# avrpwm.net
KiCad netlist of a schematic drawn in EAGLE
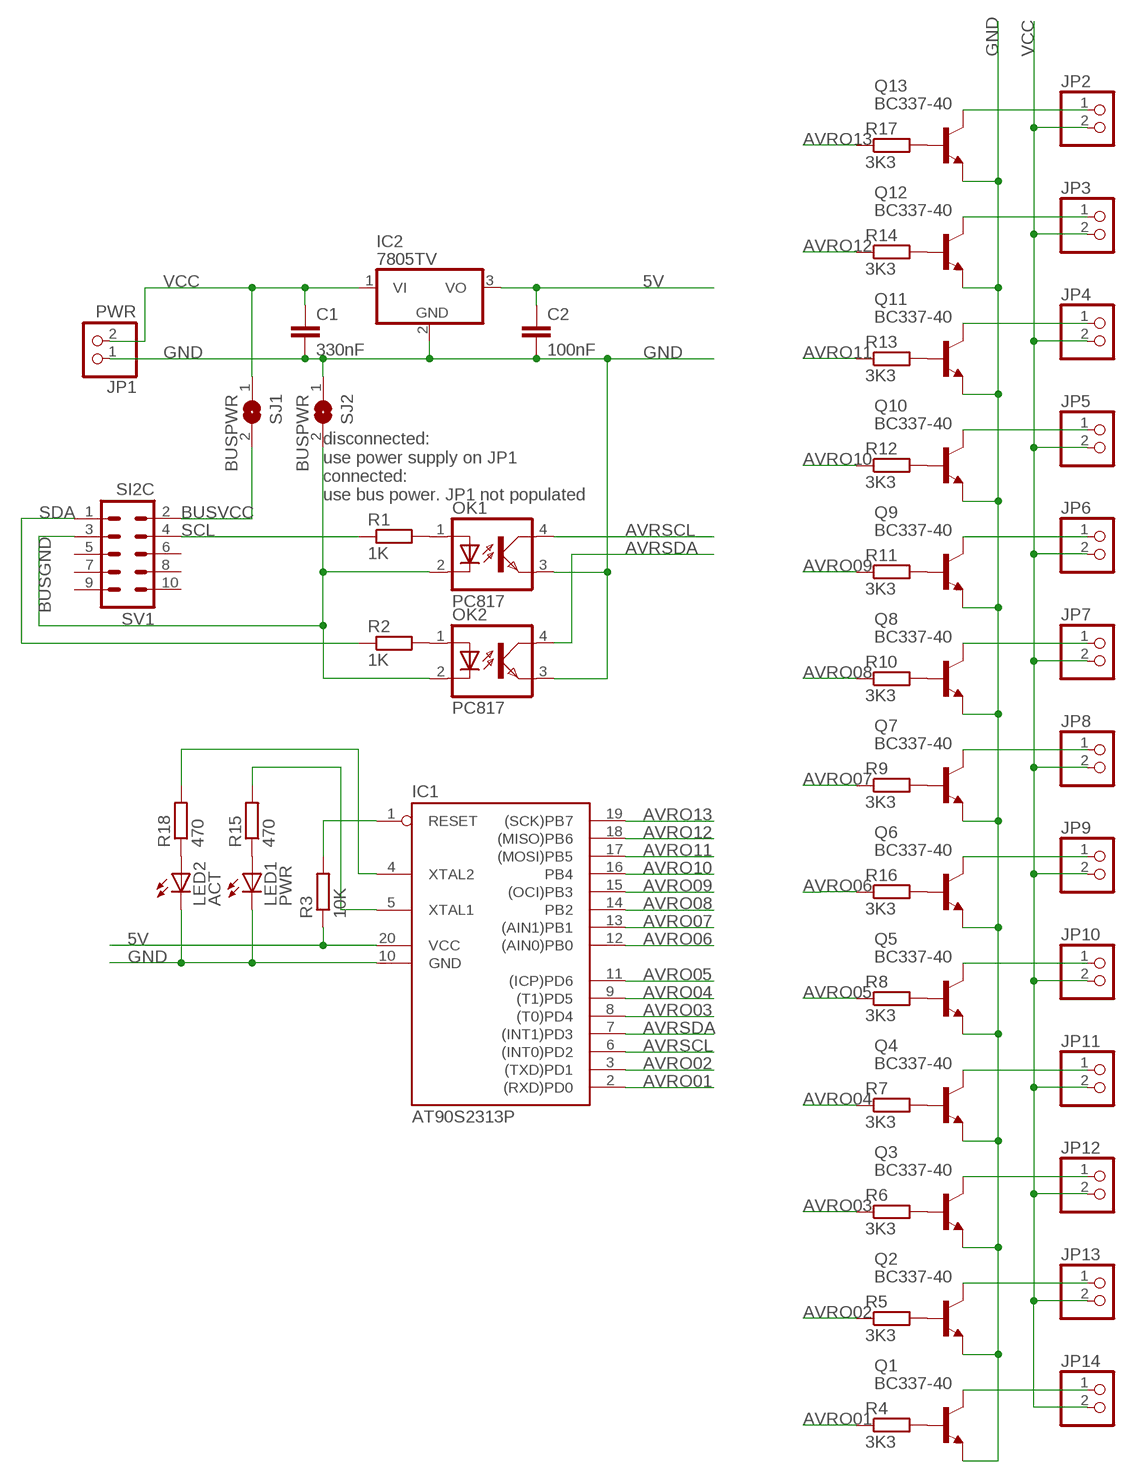
[diagram p0: schematic, sheet 1]

(export (version "E")
  (design (tool "Eeschema 10.0.6"))
  (components
    (comp (ref "C1")
      (value "330nF")
      (footprint "eagle-import:C2.5-3")
      (libsource (lib "eagle-import") (part "C2,5-3"))
    )
    (comp (ref "C2")
      (value "100nF")
      (footprint "eagle-import:C2.5-3")
      (libsource (lib "eagle-import") (part "C2,5-3"))
    )
    (comp (ref "IC1")
      (value "AT90S2313P")
      (footprint "eagle-import:DIL20")
      (libsource (lib "eagle-import") (part "AT90S2313P"))
    )
    (comp (ref "IC2")
      (value "7805TV")
      (footprint "eagle-import:TO220V")
      (libsource (lib "eagle-import") (part "78TV05"))
    )
    (comp (ref "JP1")
      (value "PWR")
      (footprint "eagle-import:1X02")
      (libsource (lib "eagle-import") (part "PINHD-1X2"))
    )
    (comp (ref "JP2")
      (value "PINHD-1X2")
      (footprint "eagle-import:1X02")
      (libsource (lib "eagle-import") (part "PINHD-1X2"))
    )
    (comp (ref "JP3")
      (value "PINHD-1X2")
      (footprint "eagle-import:1X02")
      (libsource (lib "eagle-import") (part "PINHD-1X2"))
    )
    (comp (ref "JP4")
      (value "PINHD-1X2")
      (footprint "eagle-import:1X02")
      (libsource (lib "eagle-import") (part "PINHD-1X2"))
    )
    (comp (ref "JP5")
      (value "PINHD-1X2")
      (footprint "eagle-import:1X02")
      (libsource (lib "eagle-import") (part "PINHD-1X2"))
    )
    (comp (ref "JP6")
      (value "PINHD-1X2")
      (footprint "eagle-import:1X02")
      (libsource (lib "eagle-import") (part "PINHD-1X2"))
    )
    (comp (ref "JP7")
      (value "PINHD-1X2")
      (footprint "eagle-import:1X02")
      (libsource (lib "eagle-import") (part "PINHD-1X2"))
    )
    (comp (ref "JP8")
      (value "PINHD-1X2")
      (footprint "eagle-import:1X02")
      (libsource (lib "eagle-import") (part "PINHD-1X2"))
    )
    (comp (ref "JP9")
      (value "PINHD-1X2")
      (footprint "eagle-import:1X02")
      (libsource (lib "eagle-import") (part "PINHD-1X2"))
    )
    (comp (ref "JP10")
      (value "PINHD-1X2")
      (footprint "eagle-import:1X02")
      (libsource (lib "eagle-import") (part "PINHD-1X2"))
    )
    (comp (ref "JP11")
      (value "PINHD-1X2")
      (footprint "eagle-import:1X02")
      (libsource (lib "eagle-import") (part "PINHD-1X2"))
    )
    (comp (ref "JP12")
      (value "PINHD-1X2")
      (footprint "eagle-import:1X02")
      (libsource (lib "eagle-import") (part "PINHD-1X2"))
    )
    (comp (ref "JP13")
      (value "PINHD-1X2")
      (footprint "eagle-import:1X02")
      (libsource (lib "eagle-import") (part "PINHD-1X2"))
    )
    (comp (ref "JP14")
      (value "PINHD-1X2")
      (footprint "eagle-import:1X02")
      (libsource (lib "eagle-import") (part "PINHD-1X2"))
    )
    (comp (ref "LED1")
      (value "PWR")
      (footprint "eagle-import:LED3MM")
      (libsource (lib "eagle-import") (part "LED3MM"))
    )
    (comp (ref "LED2")
      (value "ACT")
      (footprint "eagle-import:LED3MM")
      (libsource (lib "eagle-import") (part "LED3MM"))
    )
    (comp (ref "OK1")
      (value "PC817")
      (footprint "eagle-import:DIL04")
      (fields (field (name "MPN") "PC817X4J000F"))
      (libsource (lib "eagle-import") (part "PC817"))
    )
    (comp (ref "OK2")
      (value "PC817")
      (footprint "eagle-import:DIL04")
      (fields (field (name "MPN") "PC817X4J000F"))
      (libsource (lib "eagle-import") (part "PC817"))
    )
    (comp (ref "Q1")
      (value "BC337-40")
      (footprint "eagle-import:TO92")
      (libsource (lib "eagle-import") (part "BC337-40"))
    )
    (comp (ref "Q2")
      (value "BC337-40")
      (footprint "eagle-import:TO92")
      (libsource (lib "eagle-import") (part "BC337-40"))
    )
    (comp (ref "Q3")
      (value "BC337-40")
      (footprint "eagle-import:TO92")
      (libsource (lib "eagle-import") (part "BC337-40"))
    )
    (comp (ref "Q4")
      (value "BC337-40")
      (footprint "eagle-import:TO92")
      (libsource (lib "eagle-import") (part "BC337-40"))
    )
    (comp (ref "Q5")
      (value "BC337-40")
      (footprint "eagle-import:TO92")
      (libsource (lib "eagle-import") (part "BC337-40"))
    )
    (comp (ref "Q6")
      (value "BC337-40")
      (footprint "eagle-import:TO92")
      (libsource (lib "eagle-import") (part "BC337-40"))
    )
    (comp (ref "Q7")
      (value "BC337-40")
      (footprint "eagle-import:TO92")
      (libsource (lib "eagle-import") (part "BC337-40"))
    )
    (comp (ref "Q8")
      (value "BC337-40")
      (footprint "eagle-import:TO92")
      (libsource (lib "eagle-import") (part "BC337-40"))
    )
    (comp (ref "Q9")
      (value "BC337-40")
      (footprint "eagle-import:TO92")
      (libsource (lib "eagle-import") (part "BC337-40"))
    )
    (comp (ref "Q10")
      (value "BC337-40")
      (footprint "eagle-import:TO92")
      (libsource (lib "eagle-import") (part "BC337-40"))
    )
    (comp (ref "Q11")
      (value "BC337-40")
      (footprint "eagle-import:TO92")
      (libsource (lib "eagle-import") (part "BC337-40"))
    )
    (comp (ref "Q12")
      (value "BC337-40")
      (footprint "eagle-import:TO92")
      (libsource (lib "eagle-import") (part "BC337-40"))
    )
    (comp (ref "Q13")
      (value "BC337-40")
      (footprint "eagle-import:TO92")
      (libsource (lib "eagle-import") (part "BC337-40"))
    )
    (comp (ref "R1")
      (value "1K")
      (footprint "eagle-import:0207_10")
      (libsource (lib "eagle-import") (part "R-EU_0207/10"))
    )
    (comp (ref "R2")
      (value "1K")
      (footprint "eagle-import:0207_10")
      (libsource (lib "eagle-import") (part "R-EU_0207/10"))
    )
    (comp (ref "R3")
      (value "10K")
      (footprint "eagle-import:0207_10")
      (libsource (lib "eagle-import") (part "R-EU_0207/10"))
    )
    (comp (ref "R4")
      (value "3K3")
      (footprint "eagle-import:0207_10")
      (libsource (lib "eagle-import") (part "R-EU_0207/10"))
    )
    (comp (ref "R5")
      (value "3K3")
      (footprint "eagle-import:0207_10")
      (libsource (lib "eagle-import") (part "R-EU_0207/10"))
    )
    (comp (ref "R6")
      (value "3K3")
      (footprint "eagle-import:0207_10")
      (libsource (lib "eagle-import") (part "R-EU_0207/10"))
    )
    (comp (ref "R7")
      (value "3K3")
      (footprint "eagle-import:0207_10")
      (libsource (lib "eagle-import") (part "R-EU_0207/10"))
    )
    (comp (ref "R8")
      (value "3K3")
      (footprint "eagle-import:0207_10")
      (libsource (lib "eagle-import") (part "R-EU_0207/10"))
    )
    (comp (ref "R9")
      (value "3K3")
      (footprint "eagle-import:0207_10")
      (libsource (lib "eagle-import") (part "R-EU_0207/10"))
    )
    (comp (ref "R10")
      (value "3K3")
      (footprint "eagle-import:0207_10")
      (libsource (lib "eagle-import") (part "R-EU_0207/10"))
    )
    (comp (ref "R11")
      (value "3K3")
      (footprint "eagle-import:0207_10")
      (libsource (lib "eagle-import") (part "R-EU_0207/10"))
    )
    (comp (ref "R12")
      (value "3K3")
      (footprint "eagle-import:0207_10")
      (libsource (lib "eagle-import") (part "R-EU_0207/10"))
    )
    (comp (ref "R13")
      (value "3K3")
      (footprint "eagle-import:0207_10")
      (libsource (lib "eagle-import") (part "R-EU_0207/10"))
    )
    (comp (ref "R14")
      (value "3K3")
      (footprint "eagle-import:0207_10")
      (libsource (lib "eagle-import") (part "R-EU_0207/10"))
    )
    (comp (ref "R15")
      (value "470")
      (footprint "eagle-import:0207_10")
      (libsource (lib "eagle-import") (part "R-EU_0207/10"))
    )
    (comp (ref "R16")
      (value "3K3")
      (footprint "eagle-import:0207_10")
      (libsource (lib "eagle-import") (part "R-EU_0207/10"))
    )
    (comp (ref "R17")
      (value "3K3")
      (footprint "eagle-import:0207_10")
      (libsource (lib "eagle-import") (part "R-EU_0207/10"))
    )
    (comp (ref "R18")
      (value "470")
      (footprint "eagle-import:0207_10")
      (libsource (lib "eagle-import") (part "R-EU_0207/10"))
    )
    (comp (ref "SJ1")
      (value "BUSPWR")
      (footprint "eagle-import:SJ")
      (libsource (lib "eagle-import") (part "SJ"))
    )
    (comp (ref "SJ2")
      (value "BUSPWR")
      (footprint "eagle-import:SJ")
      (libsource (lib "eagle-import") (part "SJ"))
    )
    (comp (ref "SV1")
      (value "SI2C")
      (footprint "eagle-import:ML10")
      (libsource (lib "eagle-import") (part "ML10"))
    )
  )
  (nets
    (net (code "1") (name "/5V") (class "Default")
      (node (ref "C2") (pin "1") (pinfunction "1_1") (pintype "passive"))
      (node (ref "IC1") (pin "20") (pinfunction "VCC_20") (pintype "power_in"))
      (node (ref "IC2") (pin "3") (pinfunction "VO_3") (pintype "passive"))
      (node (ref "R3") (pin "1") (pinfunction "1_1") (pintype "passive"))
    )
    (net (code "2") (name "/AVRO01") (class "Default")
      (node (ref "IC1") (pin "2") (pinfunction "(RXD)PD0_2") (pintype "bidirectional"))
      (node (ref "R4") (pin "1") (pinfunction "1_1") (pintype "passive"))
    )
    (net (code "3") (name "/AVRO02") (class "Default")
      (node (ref "IC1") (pin "3") (pinfunction "(TXD)PD1_3") (pintype "bidirectional"))
      (node (ref "R5") (pin "1") (pinfunction "1_1") (pintype "passive"))
    )
    (net (code "4") (name "/AVRO03") (class "Default")
      (node (ref "IC1") (pin "8") (pinfunction "(T0)PD4_8") (pintype "bidirectional"))
      (node (ref "R6") (pin "1") (pinfunction "1_1") (pintype "passive"))
    )
    (net (code "5") (name "/AVRO04") (class "Default")
      (node (ref "IC1") (pin "9") (pinfunction "(T1)PD5_9") (pintype "bidirectional"))
      (node (ref "R7") (pin "1") (pinfunction "1_1") (pintype "passive"))
    )
    (net (code "6") (name "/AVRO05") (class "Default")
      (node (ref "IC1") (pin "11") (pinfunction "(ICP)PD6_11") (pintype "bidirectional"))
      (node (ref "R8") (pin "1") (pinfunction "1_1") (pintype "passive"))
    )
    (net (code "7") (name "/AVRO06") (class "Default")
      (node (ref "IC1") (pin "12") (pinfunction "(AIN0)PB0_12") (pintype "bidirectional"))
      (node (ref "R16") (pin "1") (pinfunction "1_1") (pintype "passive"))
    )
    (net (code "8") (name "/AVRO07") (class "Default")
      (node (ref "IC1") (pin "13") (pinfunction "(AIN1)PB1_13") (pintype "bidirectional"))
      (node (ref "R9") (pin "1") (pinfunction "1_1") (pintype "passive"))
    )
    (net (code "9") (name "/AVRO08") (class "Default")
      (node (ref "IC1") (pin "14") (pinfunction "PB2_14") (pintype "bidirectional"))
      (node (ref "R10") (pin "1") (pinfunction "1_1") (pintype "passive"))
    )
    (net (code "10") (name "/AVRO09") (class "Default")
      (node (ref "IC1") (pin "15") (pinfunction "(OCI)PB3_15") (pintype "bidirectional"))
      (node (ref "R11") (pin "1") (pinfunction "1_1") (pintype "passive"))
    )
    (net (code "11") (name "/AVRO10") (class "Default")
      (node (ref "IC1") (pin "16") (pinfunction "PB4_16") (pintype "bidirectional"))
      (node (ref "R12") (pin "1") (pinfunction "1_1") (pintype "passive"))
    )
    (net (code "12") (name "/AVRO11") (class "Default")
      (node (ref "IC1") (pin "17") (pinfunction "(MOSI)PB5_17") (pintype "bidirectional"))
      (node (ref "R13") (pin "1") (pinfunction "1_1") (pintype "passive"))
    )
    (net (code "13") (name "/AVRO12") (class "Default")
      (node (ref "IC1") (pin "18") (pinfunction "(MISO)PB6_18") (pintype "bidirectional"))
      (node (ref "R14") (pin "1") (pinfunction "1_1") (pintype "passive"))
    )
    (net (code "14") (name "/AVRO13") (class "Default")
      (node (ref "IC1") (pin "19") (pinfunction "(SCK)PB7_19") (pintype "bidirectional"))
      (node (ref "R17") (pin "1") (pinfunction "1_1") (pintype "passive"))
    )
    (net (code "15") (name "/AVRSCL") (class "Default")
      (node (ref "IC1") (pin "6") (pinfunction "(INT0)PD2_6") (pintype "bidirectional"))
      (node (ref "OK1") (pin "4") (pinfunction "COL_4") (pintype "passive"))
    )
    (net (code "16") (name "/AVRSDA") (class "Default")
      (node (ref "IC1") (pin "7") (pinfunction "(INT1)PD3_7") (pintype "bidirectional"))
      (node (ref "OK2") (pin "4") (pinfunction "COL_4") (pintype "passive"))
    )
    (net (code "17") (name "/BUSGND") (class "Default")
      (node (ref "OK1") (pin "2") (pinfunction "C_2") (pintype "passive"))
      (node (ref "OK2") (pin "2") (pinfunction "C_2") (pintype "passive"))
      (node (ref "SJ2") (pin "2") (pinfunction "2_2") (pintype "passive"))
      (node (ref "SV1") (pin "3") (pinfunction "3_3") (pintype "passive"))
    )
    (net (code "18") (name "/BUSVCC") (class "Default")
      (node (ref "SJ1") (pin "2") (pinfunction "2_2") (pintype "passive"))
      (node (ref "SV1") (pin "2") (pinfunction "2_2") (pintype "passive"))
    )
    (net (code "19") (name "/GND") (class "Default")
      (node (ref "C1") (pin "2") (pinfunction "2_2") (pintype "passive"))
      (node (ref "C2") (pin "2") (pinfunction "2_2") (pintype "passive"))
      (node (ref "IC1") (pin "10") (pinfunction "GND_10") (pintype "power_in"))
      (node (ref "IC2") (pin "2") (pinfunction "GND_2") (pintype "passive"))
      (node (ref "JP1") (pin "1") (pinfunction "1_1") (pintype "passive"))
      (node (ref "LED1") (pin "K") (pinfunction "C_K") (pintype "passive"))
      (node (ref "LED2") (pin "K") (pinfunction "C_K") (pintype "passive"))
      (node (ref "OK1") (pin "3") (pinfunction "EMIT_3") (pintype "passive"))
      (node (ref "OK2") (pin "3") (pinfunction "EMIT_3") (pintype "passive"))
      (node (ref "Q1") (pin "1") (pinfunction "E_1") (pintype "passive"))
      (node (ref "Q10") (pin "1") (pinfunction "E_1") (pintype "passive"))
      (node (ref "Q11") (pin "1") (pinfunction "E_1") (pintype "passive"))
      (node (ref "Q12") (pin "1") (pinfunction "E_1") (pintype "passive"))
      (node (ref "Q13") (pin "1") (pinfunction "E_1") (pintype "passive"))
      (node (ref "Q2") (pin "1") (pinfunction "E_1") (pintype "passive"))
      (node (ref "Q3") (pin "1") (pinfunction "E_1") (pintype "passive"))
      (node (ref "Q4") (pin "1") (pinfunction "E_1") (pintype "passive"))
      (node (ref "Q5") (pin "1") (pinfunction "E_1") (pintype "passive"))
      (node (ref "Q6") (pin "1") (pinfunction "E_1") (pintype "passive"))
      (node (ref "Q7") (pin "1") (pinfunction "E_1") (pintype "passive"))
      (node (ref "Q8") (pin "1") (pinfunction "E_1") (pintype "passive"))
      (node (ref "Q9") (pin "1") (pinfunction "E_1") (pintype "passive"))
      (node (ref "SJ2") (pin "1") (pinfunction "1_1") (pintype "passive"))
    )
    (net (code "20") (name "/SCL") (class "Default")
      (node (ref "R1") (pin "1") (pinfunction "1_1") (pintype "passive"))
      (node (ref "SV1") (pin "4") (pinfunction "4_4") (pintype "passive"))
    )
    (net (code "21") (name "/SDA") (class "Default")
      (node (ref "R2") (pin "1") (pinfunction "1_1") (pintype "passive"))
      (node (ref "SV1") (pin "1") (pinfunction "1_1") (pintype "passive"))
    )
    (net (code "22") (name "/VCC") (class "Default")
      (node (ref "C1") (pin "1") (pinfunction "1_1") (pintype "passive"))
      (node (ref "IC2") (pin "1") (pinfunction "VI_1") (pintype "input"))
      (node (ref "JP1") (pin "2") (pinfunction "2_2") (pintype "passive"))
      (node (ref "JP10") (pin "2") (pinfunction "2_2") (pintype "passive"))
      (node (ref "JP11") (pin "2") (pinfunction "2_2") (pintype "passive"))
      (node (ref "JP12") (pin "2") (pinfunction "2_2") (pintype "passive"))
      (node (ref "JP13") (pin "2") (pinfunction "2_2") (pintype "passive"))
      (node (ref "JP14") (pin "2") (pinfunction "2_2") (pintype "passive"))
      (node (ref "JP2") (pin "2") (pinfunction "2_2") (pintype "passive"))
      (node (ref "JP3") (pin "2") (pinfunction "2_2") (pintype "passive"))
      (node (ref "JP4") (pin "2") (pinfunction "2_2") (pintype "passive"))
      (node (ref "JP5") (pin "2") (pinfunction "2_2") (pintype "passive"))
      (node (ref "JP6") (pin "2") (pinfunction "2_2") (pintype "passive"))
      (node (ref "JP7") (pin "2") (pinfunction "2_2") (pintype "passive"))
      (node (ref "JP8") (pin "2") (pinfunction "2_2") (pintype "passive"))
      (node (ref "JP9") (pin "2") (pinfunction "2_2") (pintype "passive"))
      (node (ref "SJ1") (pin "1") (pinfunction "1_1") (pintype "passive"))
    )
    (net (code "23") (name "Net-(IC1-RESET)") (class "Default")
      (node (ref "IC1") (pin "1") (pinfunction "RESET_1") (pintype "bidirectional"))
      (node (ref "R3") (pin "2") (pinfunction "2_2") (pintype "passive"))
    )
    (net (code "24") (name "Net-(IC1-XTAL1)") (class "Default")
      (node (ref "IC1") (pin "5") (pinfunction "XTAL1_5") (pintype "bidirectional"))
      (node (ref "R15") (pin "2") (pinfunction "2_2") (pintype "passive"))
    )
    (net (code "25") (name "Net-(IC1-XTAL2)") (class "Default")
      (node (ref "IC1") (pin "4") (pinfunction "XTAL2_4") (pintype "bidirectional"))
      (node (ref "R18") (pin "2") (pinfunction "2_2") (pintype "passive"))
    )
    (net (code "26") (name "Net-(LED1-PadA)") (class "Default")
      (node (ref "LED1") (pin "A") (pinfunction "A_A") (pintype "passive"))
      (node (ref "R15") (pin "1") (pinfunction "1_1") (pintype "passive"))
    )
    (net (code "27") (name "Net-(LED2-PadA)") (class "Default")
      (node (ref "LED2") (pin "A") (pinfunction "A_A") (pintype "passive"))
      (node (ref "R18") (pin "1") (pinfunction "1_1") (pintype "passive"))
    )
    (net (code "28") (name "Net-(OK1-A)") (class "Default")
      (node (ref "OK1") (pin "1") (pinfunction "A_1") (pintype "passive"))
      (node (ref "R1") (pin "2") (pinfunction "2_2") (pintype "passive"))
    )
    (net (code "29") (name "Net-(OK2-A)") (class "Default")
      (node (ref "OK2") (pin "1") (pinfunction "A_1") (pintype "passive"))
      (node (ref "R2") (pin "2") (pinfunction "2_2") (pintype "passive"))
    )
    (net (code "30") (name "Net-(Q1-B)") (class "Default")
      (node (ref "Q1") (pin "2") (pinfunction "B_2") (pintype "passive"))
      (node (ref "R4") (pin "2") (pinfunction "2_2") (pintype "passive"))
    )
    (net (code "31") (name "Net-(Q1-C)") (class "Default")
      (node (ref "JP14") (pin "1") (pinfunction "1_1") (pintype "passive"))
      (node (ref "Q1") (pin "3") (pinfunction "C_3") (pintype "passive"))
    )
    (net (code "32") (name "Net-(Q2-B)") (class "Default")
      (node (ref "Q2") (pin "2") (pinfunction "B_2") (pintype "passive"))
      (node (ref "R5") (pin "2") (pinfunction "2_2") (pintype "passive"))
    )
    (net (code "33") (name "Net-(Q2-C)") (class "Default")
      (node (ref "JP13") (pin "1") (pinfunction "1_1") (pintype "passive"))
      (node (ref "Q2") (pin "3") (pinfunction "C_3") (pintype "passive"))
    )
    (net (code "34") (name "Net-(Q3-B)") (class "Default")
      (node (ref "Q3") (pin "2") (pinfunction "B_2") (pintype "passive"))
      (node (ref "R6") (pin "2") (pinfunction "2_2") (pintype "passive"))
    )
    (net (code "35") (name "Net-(Q3-C)") (class "Default")
      (node (ref "JP12") (pin "1") (pinfunction "1_1") (pintype "passive"))
      (node (ref "Q3") (pin "3") (pinfunction "C_3") (pintype "passive"))
    )
    (net (code "36") (name "Net-(Q4-B)") (class "Default")
      (node (ref "Q4") (pin "2") (pinfunction "B_2") (pintype "passive"))
      (node (ref "R7") (pin "2") (pinfunction "2_2") (pintype "passive"))
    )
    (net (code "37") (name "Net-(Q4-C)") (class "Default")
      (node (ref "JP11") (pin "1") (pinfunction "1_1") (pintype "passive"))
      (node (ref "Q4") (pin "3") (pinfunction "C_3") (pintype "passive"))
    )
    (net (code "38") (name "Net-(Q5-B)") (class "Default")
      (node (ref "Q5") (pin "2") (pinfunction "B_2") (pintype "passive"))
      (node (ref "R8") (pin "2") (pinfunction "2_2") (pintype "passive"))
    )
    (net (code "39") (name "Net-(Q5-C)") (class "Default")
      (node (ref "JP10") (pin "1") (pinfunction "1_1") (pintype "passive"))
      (node (ref "Q5") (pin "3") (pinfunction "C_3") (pintype "passive"))
    )
    (net (code "40") (name "Net-(Q6-B)") (class "Default")
      (node (ref "Q6") (pin "2") (pinfunction "B_2") (pintype "passive"))
      (node (ref "R16") (pin "2") (pinfunction "2_2") (pintype "passive"))
    )
    (net (code "41") (name "Net-(Q6-C)") (class "Default")
      (node (ref "JP9") (pin "1") (pinfunction "1_1") (pintype "passive"))
      (node (ref "Q6") (pin "3") (pinfunction "C_3") (pintype "passive"))
    )
    (net (code "42") (name "Net-(Q7-B)") (class "Default")
      (node (ref "Q7") (pin "2") (pinfunction "B_2") (pintype "passive"))
      (node (ref "R9") (pin "2") (pinfunction "2_2") (pintype "passive"))
    )
    (net (code "43") (name "Net-(Q7-C)") (class "Default")
      (node (ref "JP8") (pin "1") (pinfunction "1_1") (pintype "passive"))
      (node (ref "Q7") (pin "3") (pinfunction "C_3") (pintype "passive"))
    )
    (net (code "44") (name "Net-(Q8-B)") (class "Default")
      (node (ref "Q8") (pin "2") (pinfunction "B_2") (pintype "passive"))
      (node (ref "R10") (pin "2") (pinfunction "2_2") (pintype "passive"))
    )
    (net (code "45") (name "Net-(Q8-C)") (class "Default")
      (node (ref "JP7") (pin "1") (pinfunction "1_1") (pintype "passive"))
      (node (ref "Q8") (pin "3") (pinfunction "C_3") (pintype "passive"))
    )
    (net (code "46") (name "Net-(Q9-B)") (class "Default")
      (node (ref "Q9") (pin "2") (pinfunction "B_2") (pintype "passive"))
      (node (ref "R11") (pin "2") (pinfunction "2_2") (pintype "passive"))
    )
    (net (code "47") (name "Net-(Q9-C)") (class "Default")
      (node (ref "JP6") (pin "1") (pinfunction "1_1") (pintype "passive"))
      (node (ref "Q9") (pin "3") (pinfunction "C_3") (pintype "passive"))
    )
    (net (code "48") (name "Net-(Q10-B)") (class "Default")
      (node (ref "Q10") (pin "2") (pinfunction "B_2") (pintype "passive"))
      (node (ref "R12") (pin "2") (pinfunction "2_2") (pintype "passive"))
    )
    (net (code "49") (name "Net-(Q10-C)") (class "Default")
      (node (ref "JP5") (pin "1") (pinfunction "1_1") (pintype "passive"))
      (node (ref "Q10") (pin "3") (pinfunction "C_3") (pintype "passive"))
    )
    (net (code "50") (name "Net-(Q11-B)") (class "Default")
      (node (ref "Q11") (pin "2") (pinfunction "B_2") (pintype "passive"))
      (node (ref "R13") (pin "2") (pinfunction "2_2") (pintype "passive"))
    )
    (net (code "51") (name "Net-(Q11-C)") (class "Default")
      (node (ref "JP4") (pin "1") (pinfunction "1_1") (pintype "passive"))
      (node (ref "Q11") (pin "3") (pinfunction "C_3") (pintype "passive"))
    )
    (net (code "52") (name "Net-(Q12-B)") (class "Default")
      (node (ref "Q12") (pin "2") (pinfunction "B_2") (pintype "passive"))
      (node (ref "R14") (pin "2") (pinfunction "2_2") (pintype "passive"))
    )
    (net (code "53") (name "Net-(Q12-C)") (class "Default")
      (node (ref "JP3") (pin "1") (pinfunction "1_1") (pintype "passive"))
      (node (ref "Q12") (pin "3") (pinfunction "C_3") (pintype "passive"))
    )
    (net (code "54") (name "Net-(Q13-B)") (class "Default")
      (node (ref "Q13") (pin "2") (pinfunction "B_2") (pintype "passive"))
      (node (ref "R17") (pin "2") (pinfunction "2_2") (pintype "passive"))
    )
    (net (code "55") (name "Net-(Q13-C)") (class "Default")
      (node (ref "JP2") (pin "1") (pinfunction "1_1") (pintype "passive"))
      (node (ref "Q13") (pin "3") (pinfunction "C_3") (pintype "passive"))
    )
    (net (code "56") (name "unconnected-(SV1-Pad5)") (class "Default")
      (node (ref "SV1") (pin "5") (pinfunction "5_5") (pintype "passive"))
    )
    (net (code "57") (name "unconnected-(SV1-Pad6)") (class "Default")
      (node (ref "SV1") (pin "6") (pinfunction "6_6") (pintype "passive"))
    )
    (net (code "58") (name "unconnected-(SV1-Pad7)") (class "Default")
      (node (ref "SV1") (pin "7") (pinfunction "7_7") (pintype "passive"))
    )
    (net (code "59") (name "unconnected-(SV1-Pad8)") (class "Default")
      (node (ref "SV1") (pin "8") (pinfunction "8_8") (pintype "passive"))
    )
    (net (code "60") (name "unconnected-(SV1-Pad9)") (class "Default")
      (node (ref "SV1") (pin "9") (pinfunction "9_9") (pintype "passive"))
    )
    (net (code "61") (name "unconnected-(SV1-Pad10)") (class "Default")
      (node (ref "SV1") (pin "10") (pinfunction "10_10") (pintype "passive"))
    )
  )
)
